# charger.net
KiCad netlist of a schematic drawn in Altium Designer
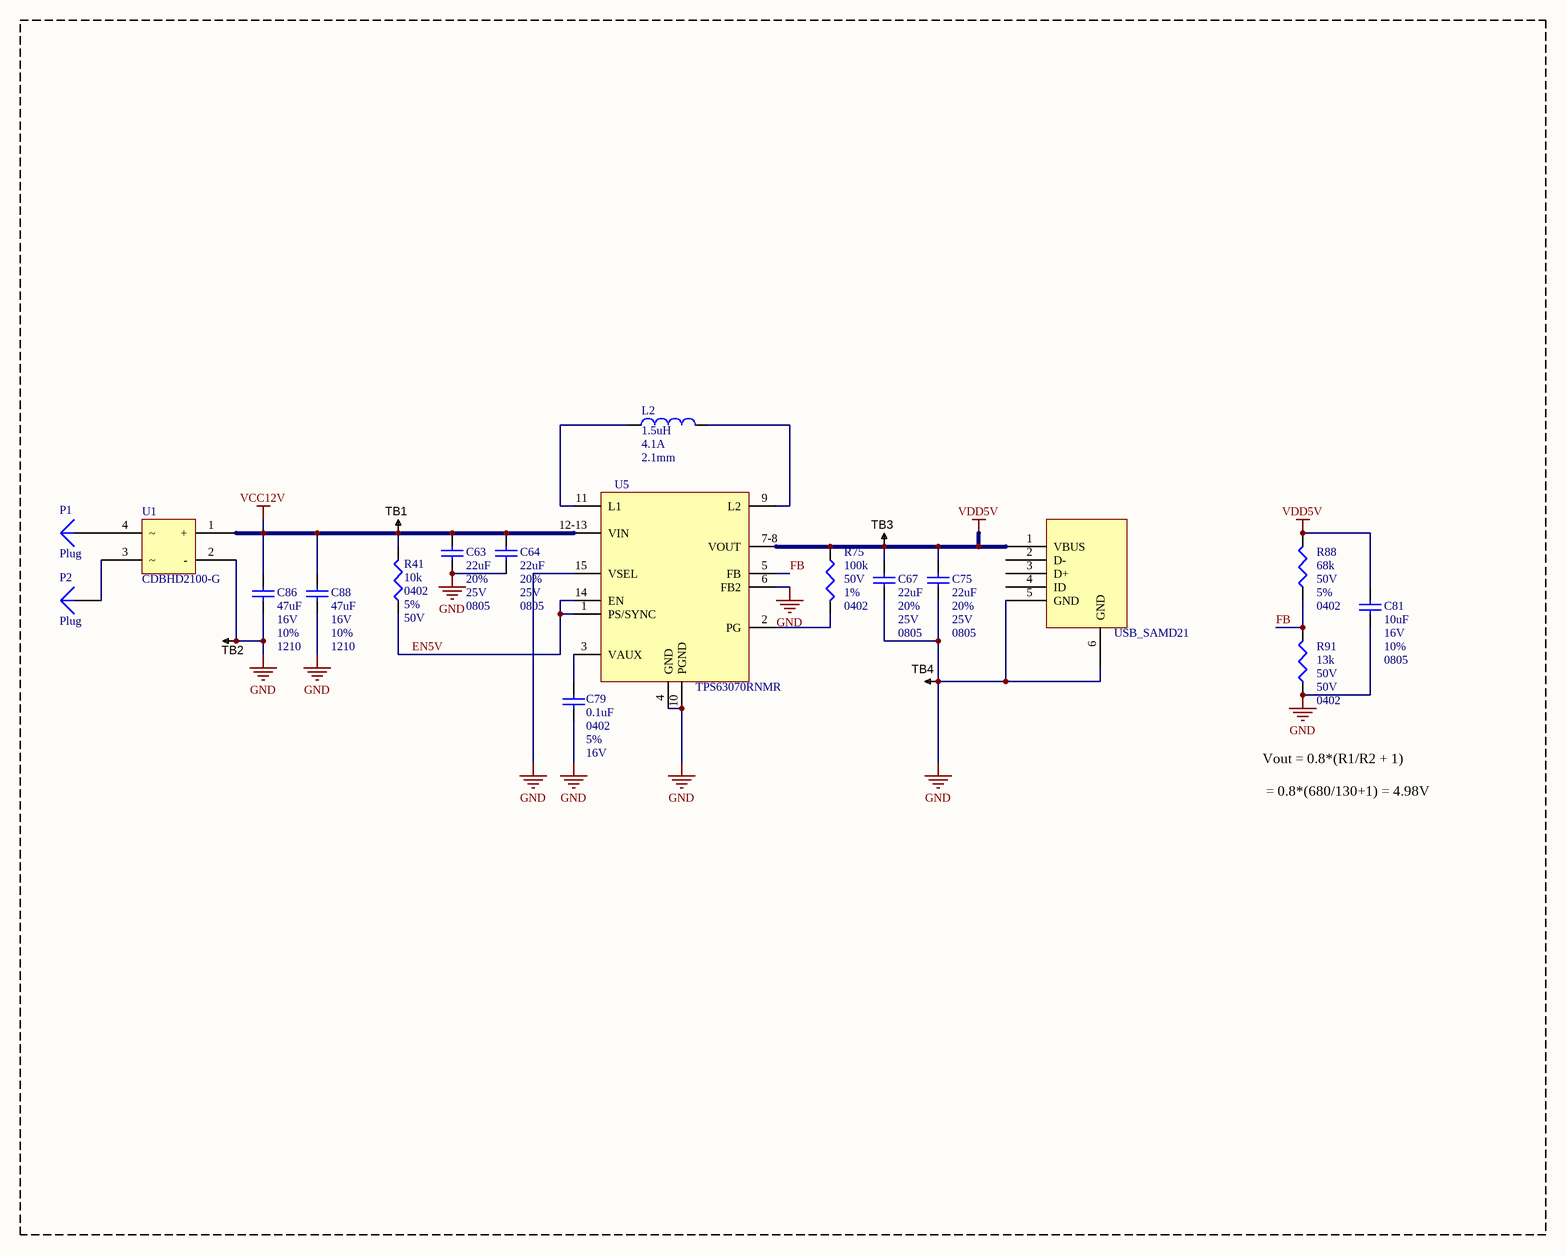
[diagram p0: charger.SchDoc]

(export (version "E")
  (design (tool "Eeschema 10.0.6"))
  (components
    (comp (ref "C63")
      (value "22uF")
      (footprint "C0805")
      (description "Capacitor (Semiconductor SIM Model)")
      (fields
        (field (name "MANUFACTURER") "Murata")
        (field (name "MANUFACTURER PART NUMBER") "GRM21BR61E226ME44K")
        (field (name "CASE/PACKAGE") "0805")
        (field (name "VOLTAGE RATING") "25V")
        (field (name "TOLERANCE") "20%")
      )
      (libsource (lib "Miscellaneous Devices") (part "Cap Semi"))
    )
    (comp (ref "C64")
      (value "22uF")
      (footprint "C0805")
      (description "Capacitor (Semiconductor SIM Model)")
      (fields
        (field (name "MANUFACTURER") "Murata")
        (field (name "MANUFACTURER PART NUMBER") "GRM21BR61E226ME44K")
        (field (name "CASE/PACKAGE") "0805")
        (field (name "VOLTAGE RATING") "25V")
        (field (name "TOLERANCE") "20%")
      )
      (libsource (lib "Miscellaneous Devices") (part "Cap Semi"))
    )
    (comp (ref "C67")
      (value "22uF")
      (footprint "C0805")
      (description "Capacitor (Semiconductor SIM Model)")
      (fields
        (field (name "MANUFACTURER") "Murata")
        (field (name "MANUFACTURER PART NUMBER") "GRM21BR61E226ME44K")
        (field (name "CASE/PACKAGE") "0805")
        (field (name "VOLTAGE RATING") "25V")
        (field (name "TOLERANCE") "20%")
      )
      (libsource (lib "Miscellaneous Devices") (part "Cap Semi"))
    )
    (comp (ref "C75")
      (value "22uF")
      (footprint "C0805")
      (description "Capacitor (Semiconductor SIM Model)")
      (fields
        (field (name "MANUFACTURER") "Murata")
        (field (name "MANUFACTURER PART NUMBER") "GRM21BR61E226ME44K")
        (field (name "CASE/PACKAGE") "0805")
        (field (name "VOLTAGE RATING") "25V")
        (field (name "TOLERANCE") "20%")
      )
      (libsource (lib "Miscellaneous Devices") (part "Cap Semi"))
    )
    (comp (ref "C79")
      (value "0.1uF")
      (footprint "C0402")
      (description "Capacitor (Semiconductor SIM Model)")
      (fields
        (field (name "MANUFACTURER") "Yageo")
        (field (name "MANUFACTURER PART NUMBER") "CC0402JRX7R7BB104")
        (field (name "CASE CODE (IMPERIAL)") "0402")
        (field (name "TOLERANCE") "5%")
        (field (name "VOLTAGE RATING") "16V")
      )
      (libsource (lib "Miscellaneous Devices") (part "Cap Semi"))
    )
    (comp (ref "C81")
      (value "10uF")
      (footprint "C0805")
      (description "Capacitor")
      (fields
        (field (name "MANUFACTURER") "Samsung")
        (field (name "MANUFACTURER PART NUMBER") "CL21A106KOQNNNG")
        (field (name "CASE/PACKAGE") "0805")
        (field (name "TOLERANCE") "10%")
        (field (name "VOLTAGE") "16V")
      )
      (libsource (lib "Miscellaneous Devices") (part "Cap Semi"))
    )
    (comp (ref "C86")
      (value "47uF")
      (footprint "C1210")
      (description "Capacitor (Semiconductor SIM Model)")
      (fields
        (field (name "MANUFACTURER") "Murata")
        (field (name "MANUFACTURER PART NUMBER") "GRM32EC81C476KE15L")
        (field (name "CASE/PACKAGE") "1210")
        (field (name "TOLERANCE") "10%")
        (field (name "VOLTAGE") "16V")
      )
      (libsource (lib "Miscellaneous Devices") (part "Cap Semi"))
    )
    (comp (ref "C88")
      (value "47uF")
      (footprint "C1210")
      (description "Capacitor (Semiconductor SIM Model)")
      (fields
        (field (name "MANUFACTURER") "Murata")
        (field (name "MANUFACTURER PART NUMBER") "GRM32EC81C476KE15L")
        (field (name "CASE/PACKAGE") "1210")
        (field (name "TOLERANCE") "10%")
        (field (name "VOLTAGE") "16V")
      )
      (libsource (lib "Miscellaneous Devices") (part "Cap Semi"))
    )
    (comp (ref "L2")
      (value "1.5uH")
      (footprint "INDM4040X210")
      (description "Inductor")
      (fields
        (field (name "MANUFACTURER") "Coilcraft")
        (field (name "MANUFACTURER PART NUMBER") "XFL4020-152MEC")
        (field (name "SATURATION CURRENT") "4.1A")
        (field (name "HEIGHT") "2.1mm")
      )
      (libsource (lib "Miscellaneous Devices") (part "Inductor"))
    )
    (comp (ref "P1")
      (value "Plug")
      (footprint "Pogo_RightAngle")
      (fields (field (name "PUBLISHER") "Altium Limited"))
      (libsource (lib "Miscellaneous Connectors") (part "Plug"))
    )
    (comp (ref "P2")
      (value "Plug")
      (footprint "Pogo_RightAngle")
      (fields (field (name "PUBLISHER") "Altium Limited"))
      (libsource (lib "Miscellaneous Connectors") (part "Plug"))
    )
    (comp (ref "R41")
      (value "10k")
      (footprint "R0402")
      (description "Resistor")
      (fields
        (field (name "MANUFACTURER") "TE Connectivity")
        (field (name "MANUFACTURER PART NUMBER") "CRG0402J10K/10")
        (field (name "CASE/PACKAGE") "0402")
        (field (name "TOLERANCE") "5%")
        (field (name "VOLTAGE RATING") "50V")
      )
      (libsource (lib "Miscellaneous Devices") (part "Res3"))
    )
    (comp (ref "R75")
      (value "100k")
      (footprint "R0402")
      (description "Resistor")
      (fields
        (field (name "MANUFACTURER") "Yageo")
        (field (name "MANUFACTURER PART NUMBER") "RC0402FR-07100KL")
        (field (name "CASE/PACKAGE") "0402")
        (field (name "TOLERANCE") "1%")
        (field (name "VOLTAGE RATING") "50V")
      )
      (libsource (lib "Miscellaneous Devices") (part "Res3"))
    )
    (comp (ref "R88")
      (value "68k")
      (footprint "R0402")
      (description "Resistor")
      (fields
        (field (name "MANUFACTURER") "Yageo")
        (field (name "MANUFACTURER PART NUMBER") "RC0402JR-0768KL")
        (field (name "CASE/PACKAGE") "0402")
        (field (name "TOLERANCE") "5%")
        (field (name "VOLTAGE RATING") "50V")
      )
      (libsource (lib "Miscellaneous Devices") (part "Res3"))
    )
    (comp (ref "R91")
      (value "13k")
      (footprint "R0402")
      (description "Resistor")
      (fields
        (field (name "MANUFACTURER") "Yageo")
        (field (name "MANUFACTURER PART NUMBER") "RC0402FR-0713KL")
        (field (name "CASE/PACKAGE") "0402")
        (field (name "VOLTAGE RATING") "50V")
        (field (name "VOLTAGE RATING (DC)") "50V")
      )
      (libsource (lib "Miscellaneous Devices") (part "Res3"))
    )
    (comp (ref "TB1")
      (value "TESTPOINT")
      (footprint "TP-R40")
      (description "SMD test pin")
      (libsource (lib "PBL - Test Points") (part "TESTPOINT"))
    )
    (comp (ref "TB2")
      (value "TESTPOINT")
      (footprint "TP-R40")
      (description "SMD test pin")
      (libsource (lib "PBL - Test Points") (part "TESTPOINT"))
    )
    (comp (ref "TB3")
      (value "TESTPOINT")
      (footprint "TP-R40")
      (description "SMD test pin")
      (libsource (lib "PBL - Test Points") (part "TESTPOINT"))
    )
    (comp (ref "TB4")
      (value "TESTPOINT")
      (footprint "TP-R40")
      (description "SMD test pin")
      (libsource (lib "PBL - Test Points") (part "TESTPOINT"))
    )
    (comp (ref "U1")
      (value "CDBHD2100-G")
      (footprint "CDBHD2100-G")
      (description "DIODE BRIDGE 2A 100V TO-269AA")
      (fields (field (name "MANUFACTURER") "Comchip"))
      (libsource (lib "Schlib1") (part "DIODE_BRIDGE_100V_2A"))
    )
    (comp (ref "U5")
      (value "TPS63070RNMR")
      (footprint "QFN50P250X300X100-15N_TPS63070RNMR(Primary)")
      (description "Wide Input Voltage _2V-16V_ Buck-Boost Converter 15-VQFN-HR")
      (fields (field (name "DIGI-KEY_PART_NUMBER") "296-44874-1-ND") (field (name "MF") "Texas Instruments"))
      (libsource (lib "Schlib1") (part "TPS63070RNMR"))
    )
    (comp (ref "USB_SAMD21")
      (value "USB MICRO SMD")
      (footprint "MicroUSB B Plug")
      (description "CONN RCPT USB MICRO AB SMD R/A")
      (libsource (lib "Schlib1") (part "USB MICRO SMD"))
    )
  )
  (nets
    (net (code "1") (name "/EN5V") (class "Default")
      (node (ref "R41") (pin "1") (pinfunction "1_1") (pintype "passive"))
      (node (ref "U5") (pin "1") (pinfunction "PS/SYNC_1") (pintype "passive"))
      (node (ref "U5") (pin "14") (pinfunction "EN_14") (pintype "passive"))
    )
    (net (code "2") (name "/FB") (class "Default")
      (node (ref "R88") (pin "1") (pinfunction "1_1") (pintype "passive"))
      (node (ref "R91") (pin "2") (pinfunction "2_2") (pintype "passive"))
      (node (ref "U5") (pin "5") (pinfunction "FB_5") (pintype "passive"))
    )
    (net (code "3") (name "GND") (class "Default")
      (node (ref "C63") (pin "1") (pinfunction "1_1") (pintype "passive"))
      (node (ref "C64") (pin "1") (pinfunction "1_1") (pintype "passive"))
      (node (ref "C67") (pin "1") (pinfunction "1_1") (pintype "passive"))
      (node (ref "C75") (pin "1") (pinfunction "1_1") (pintype "passive"))
      (node (ref "C79") (pin "2") (pinfunction "2_2") (pintype "passive"))
      (node (ref "C81") (pin "1") (pinfunction "1_1") (pintype "passive"))
      (node (ref "C86") (pin "1") (pinfunction "1_1") (pintype "passive"))
      (node (ref "C88") (pin "1") (pinfunction "1_1") (pintype "passive"))
      (node (ref "R91") (pin "1") (pinfunction "1_1") (pintype "passive"))
      (node (ref "TB2") (pin "1") (pintype "passive"))
      (node (ref "TB4") (pin "1") (pintype "passive"))
      (node (ref "U1") (pin "2") (pinfunction "-_2") (pintype "passive"))
      (node (ref "U5") (pin "10") (pinfunction "PGND_10") (pintype "passive"))
      (node (ref "U5") (pin "15") (pinfunction "VSEL_15") (pintype "passive"))
      (node (ref "U5") (pin "4") (pinfunction "GND_4") (pintype "passive"))
      (node (ref "U5") (pin "6") (pinfunction "FB2_6") (pintype "passive"))
      (node (ref "USB_SAMD21") (pin "5") (pinfunction "GND_5") (pintype "passive"))
      (node (ref "USB_SAMD21") (pin "6") (pinfunction "GND_6") (pintype "passive"))
    )
    (net (code "4") (name "Net-(P1-Pad1)") (class "Default")
      (node (ref "P1") (pin "1") (pinfunction "1_1") (pintype "passive"))
      (node (ref "U1") (pin "4") (pinfunction "~_4") (pintype "passive"))
    )
    (net (code "5") (name "Net-(P2-Pad1)") (class "Default")
      (node (ref "P2") (pin "1") (pinfunction "1_1") (pintype "passive"))
      (node (ref "U1") (pin "3") (pinfunction "~_3") (pintype "passive"))
    )
    (net (code "6") (name "Net-(U5-L1)") (class "Default")
      (node (ref "L2") (pin "1") (pinfunction "1_1") (pintype "passive"))
      (node (ref "U5") (pin "11") (pinfunction "L1_11") (pintype "passive"))
    )
    (net (code "7") (name "Net-(U5-L2)") (class "Default")
      (node (ref "L2") (pin "2") (pinfunction "2_2") (pintype "passive"))
      (node (ref "U5") (pin "9") (pinfunction "L2_9") (pintype "passive"))
    )
    (net (code "8") (name "Net-(U5-PG)") (class "Default")
      (node (ref "R75") (pin "2") (pinfunction "2_2") (pintype "passive"))
      (node (ref "U5") (pin "2") (pinfunction "PG_2") (pintype "passive"))
    )
    (net (code "9") (name "Net-(U5-VAUX)") (class "Default")
      (node (ref "C79") (pin "1") (pinfunction "1_1") (pintype "passive"))
      (node (ref "U5") (pin "3") (pinfunction "VAUX_3") (pintype "passive"))
    )
    (net (code "10") (name "VCC12V") (class "Default")
      (node (ref "C63") (pin "2") (pinfunction "2_2") (pintype "passive"))
      (node (ref "C64") (pin "2") (pinfunction "2_2") (pintype "passive"))
      (node (ref "C86") (pin "2") (pinfunction "2_2") (pintype "passive"))
      (node (ref "C88") (pin "2") (pinfunction "2_2") (pintype "passive"))
      (node (ref "R41") (pin "2") (pinfunction "2_2") (pintype "passive"))
      (node (ref "TB1") (pin "1") (pintype "passive"))
      (node (ref "U1") (pin "1") (pinfunction "+_1") (pintype "passive"))
      (node (ref "U5") (pin "12-13") (pinfunction "VIN_12-13") (pintype "passive"))
    )
    (net (code "11") (name "VDD5V") (class "Default")
      (node (ref "C67") (pin "2") (pinfunction "2_2") (pintype "passive"))
      (node (ref "C75") (pin "2") (pinfunction "2_2") (pintype "passive"))
      (node (ref "C81") (pin "2") (pinfunction "2_2") (pintype "passive"))
      (node (ref "R75") (pin "1") (pinfunction "1_1") (pintype "passive"))
      (node (ref "R88") (pin "2") (pinfunction "2_2") (pintype "passive"))
      (node (ref "TB3") (pin "1") (pintype "passive"))
      (node (ref "U5") (pin "7-8") (pinfunction "VOUT_7-8") (pintype "passive"))
      (node (ref "USB_SAMD21") (pin "1") (pinfunction "VBUS_1") (pintype "passive"))
    )
    (net (code "12") (name "unconnected-(USB_SAMD21-D+-Pad3)") (class "Default")
      (node (ref "USB_SAMD21") (pin "3") (pinfunction "D+_3") (pintype "passive"))
    )
    (net (code "13") (name "unconnected-(USB_SAMD21-D--Pad2)") (class "Default")
      (node (ref "USB_SAMD21") (pin "2") (pinfunction "D-_2") (pintype "passive"))
    )
    (net (code "14") (name "unconnected-(USB_SAMD21-ID-Pad4)") (class "Default")
      (node (ref "USB_SAMD21") (pin "4") (pinfunction "ID_4") (pintype "passive"))
    )
  )
)
